# FLASH.net
KiCad netlist of a schematic drawn in Altium Designer
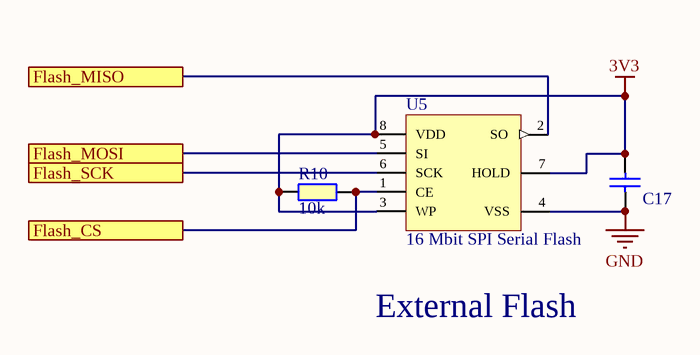
[diagram p0: FLASH.SchDoc]

(export (version "E")
  (design (tool "Eeschema 10.0.6"))
  (components
    (comp (ref "C17") (value "0.01uF") (footprint "C_0603") (libsource (lib "Node") (part "CAP_0603")))
    (comp (ref "R10") (value "10k") (footprint "R_0603") (libsource (lib "Node") (part "RES_0603")))
    (comp (ref "U5")
      (value "16 Mbit SPI Serial Flash")
      (footprint "ThanhNT:SOIC127P790X216-8N")
      (fields (field (name "MPN") "SST25VF016B-50-4I-S2AF"))
      (libsource (lib "ThanhNT") (part "SST25VF016B"))
    )
  )
  (nets
    (net (code "1") (name "/Flash_CS") (class "Default")
      (node (ref "R10") (pin "1") (pinfunction "1_1") (pintype "passive"))
      (node (ref "U5") (pin "1") (pinfunction "CE_1") (pintype "passive"))
    )
    (net (code "2") (name "/Flash_MISO") (class "Default")
      (node (ref "U5") (pin "2") (pinfunction "SO_2") (pintype "output"))
    )
    (net (code "3") (name "/Flash_MOSI") (class "Default")
      (node (ref "U5") (pin "5") (pinfunction "SI_5") (pintype "passive"))
    )
    (net (code "4") (name "/Flash_SCK") (class "Default")
      (node (ref "U5") (pin "6") (pinfunction "SCK_6") (pintype "passive"))
    )
    (net (code "5") (name "3V3") (class "Default")
      (node (ref "C17") (pin "2") (pinfunction "2_2") (pintype "passive"))
      (node (ref "R10") (pin "2") (pinfunction "2_2") (pintype "passive"))
      (node (ref "U5") (pin "3") (pinfunction "WP_3") (pintype "passive"))
      (node (ref "U5") (pin "7") (pinfunction "HOLD_7") (pintype "passive"))
      (node (ref "U5") (pin "8") (pinfunction "VDD_8") (pintype "power_in"))
    )
    (net (code "6") (name "GND") (class "Default")
      (node (ref "C17") (pin "1") (pinfunction "1_1") (pintype "passive"))
      (node (ref "U5") (pin "4") (pinfunction "VSS_4") (pintype "passive"))
    )
  )
)
